# Super-Regenerative-FM-Tuner-ForcedQuench.net
KiCad netlist of a schematic drawn in EAGLE
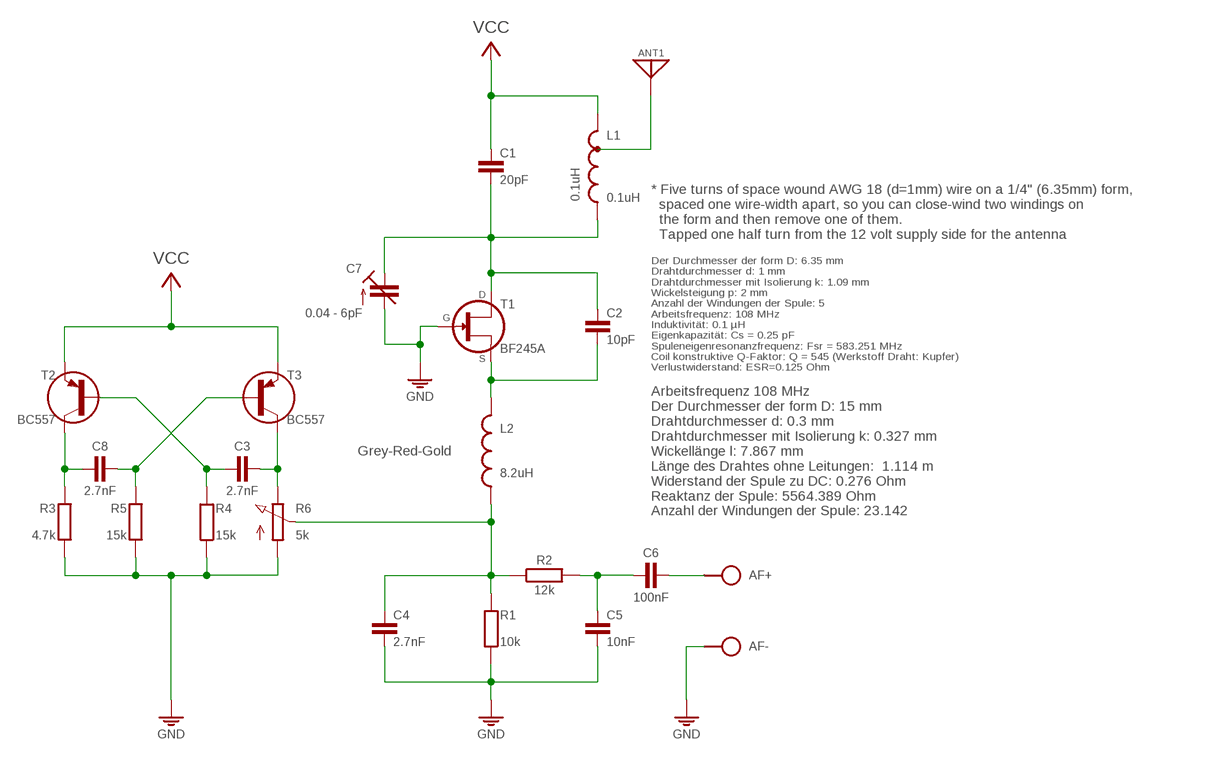
[diagram p0: schematic, sheet 1]

(export (version "E")
  (design (tool "Eeschema 10.0.6"))
  (components
    (comp (ref "AF")
      (value "SPAD+-+-")
      (footprint "eagle-import:SPAD+-")
      (libsource (lib "eagle-import") (part "SPAD+-+-"))
    )
    (comp (ref "ANT1")
      (value "ANT")
      (footprint "eagle-import:SPAD")
      (libsource (lib "eagle-import") (part "ANT"))
    )
    (comp (ref "C1")
      (value "20pF")
      (footprint "eagle-import:C025-015X024")
      (libsource (lib "eagle-import") (part "C025-015X024"))
    )
    (comp (ref "C2")
      (value "10pF")
      (footprint "eagle-import:C025-015X024")
      (libsource (lib "eagle-import") (part "C025-015X024"))
    )
    (comp (ref "C3")
      (value "2.7nF")
      (footprint "eagle-import:C0750-020X044")
      (libsource (lib "eagle-import") (part "C-H075-020X044"))
    )
    (comp (ref "C4")
      (value "2.7nF")
      (footprint "eagle-import:C050-020X044@1")
      (libsource (lib "eagle-import") (part "C050-020X044"))
    )
    (comp (ref "C5")
      (value "10nF")
      (footprint "eagle-import:C050-020X044@1")
      (libsource (lib "eagle-import") (part "C050-020X044"))
    )
    (comp (ref "C6")
      (value "100nF")
      (footprint "eagle-import:C050-020X044")
      (libsource (lib "eagle-import") (part "C-H050-020X044"))
    )
    (comp (ref "C7")
      (value "0.04 - 6pF")
      (footprint "eagle-import:CTRIMTZ03")
      (libsource (lib "eagle-import") (part "C-TR-PH20127-TZ03"))
    )
    (comp (ref "C8")
      (value "2.7nF")
      (footprint "eagle-import:C0750-020X044")
      (libsource (lib "eagle-import") (part "C-H075-020X044"))
    )
    (comp (ref "L1")
      (value "0.1uH")
      (footprint "eagle-import:L-08_12-TAP1")
      (libsource (lib "eagle-import") (part "L-TAP1L-08/12-TAP1"))
    )
    (comp (ref "L2")
      (value "8.2uH")
      (footprint "eagle-import:L-04_7-V")
      (libsource (lib "eagle-import") (part "L04/7-V"))
    )
    (comp (ref "PWR")
      (value "VCC_GNDL")
      (footprint "eagle-import:SPAD-+")
      (libsource (lib "eagle-import") (part "VCC_GNDL"))
    )
    (comp (ref "R1")
      (value "10k")
      (footprint "eagle-import:0204_7")
      (libsource (lib "eagle-import") (part "R0204/7"))
    )
    (comp (ref "R2")
      (value "12k")
      (footprint "eagle-import:0204_7")
      (libsource (lib "eagle-import") (part "R-H0204/7"))
    )
    (comp (ref "R3")
      (value "4.7k")
      (footprint "eagle-import:0202_7-V")
      (libsource (lib "eagle-import") (part "R0202/7-V"))
    )
    (comp (ref "R4")
      (value "15k")
      (footprint "eagle-import:0202_7-V")
      (libsource (lib "eagle-import") (part "R0202/7-V"))
    )
    (comp (ref "R5")
      (value "15k")
      (footprint "eagle-import:0202_7-V")
      (libsource (lib "eagle-import") (part "R0202/7-V"))
    )
    (comp (ref "R6")
      (value "5k")
      (footprint "eagle-import:POT-V")
      (libsource (lib "eagle-import") (part "POT-V"))
    )
    (comp (ref "T1")
      (value "BF245A")
      (footprint "eagle-import:TO92-GSD")
      (libsource (lib "eagle-import") (part "BF245BTO92"))
    )
    (comp (ref "T2")
      (value "BC557")
      (footprint "eagle-import:TO92-CBE")
      (libsource (lib "eagle-import") (part "BC557CBE"))
    )
    (comp (ref "T3")
      (value "BC557")
      (footprint "eagle-import:TO92-CBE")
      (libsource (lib "eagle-import") (part "BC557CBE"))
    )
  )
  (nets
    (net (code "1") (name "GND") (class "Default")
      (node (ref "AF") (pin "1") (pinfunction "P$1_1") (pintype "passive"))
      (node (ref "C4") (pin "2") (pinfunction "2_2") (pintype "passive"))
      (node (ref "C5") (pin "2") (pinfunction "2_2") (pintype "passive"))
      (node (ref "C7") (pin "1") (pinfunction "A_1") (pintype "passive"))
      (node (ref "PWR") (pin "1") (pinfunction "GND_1") (pintype "power_in"))
      (node (ref "R1") (pin "1") (pinfunction "2_1") (pintype "passive"))
      (node (ref "R3") (pin "1") (pinfunction "2_1") (pintype "passive"))
      (node (ref "R4") (pin "1") (pinfunction "2_1") (pintype "passive"))
      (node (ref "R5") (pin "1") (pinfunction "2_1") (pintype "passive"))
      (node (ref "R6") (pin "A") (pinfunction "A_A") (pintype "passive"))
      (node (ref "T1") (pin "1") (pinfunction "G_1") (pintype "passive"))
    )
    (net (code "2") (name "Net-(AFA-P$1)") (class "Default")
      (node (ref "AF") (pin "2") (pinfunction "P$1_2") (pintype "passive"))
      (node (ref "C6") (pin "2") (pinfunction "2_2") (pintype "passive"))
    )
    (net (code "3") (name "Net-(C3-Pad2)") (class "Default")
      (node (ref "C3") (pin "2") (pinfunction "2_2") (pintype "passive"))
      (node (ref "R6") (pin "E") (pinfunction "E_E") (pintype "passive"))
      (node (ref "T3") (pin "C") (pinfunction "C_C") (pintype "passive"))
    )
    (net (code "4") (name "Net-(C5-Pad1)") (class "Default")
      (node (ref "C5") (pin "1") (pinfunction "1_1") (pintype "passive"))
      (node (ref "C6") (pin "1") (pinfunction "1_1") (pintype "passive"))
      (node (ref "R2") (pin "2") (pinfunction "2_2") (pintype "passive"))
    )
    (net (code "5") (name "Net-(C7-E)") (class "Default")
      (node (ref "C1") (pin "2") (pinfunction "2_2") (pintype "passive"))
      (node (ref "C2") (pin "1") (pinfunction "1_1") (pintype "passive"))
      (node (ref "C7") (pin "2") (pinfunction "E_2") (pintype "passive"))
      (node (ref "L1") (pin "2") (pinfunction "2_2") (pintype "passive"))
      (node (ref "T1") (pin "3") (pinfunction "D_3") (pintype "passive"))
    )
    (net (code "6") (name "Net-(L1-T)") (class "Default")
      (node (ref "ANT1") (pin "1") (pinfunction "1_1") (pintype "output"))
      (node (ref "L1") (pin "3") (pinfunction "T_3") (pintype "passive"))
    )
    (net (code "7") (name "Net-(R1-1)") (class "Default")
      (node (ref "C4") (pin "1") (pinfunction "1_1") (pintype "passive"))
      (node (ref "L2") (pin "2") (pinfunction "2_2") (pintype "passive"))
      (node (ref "R1") (pin "2") (pinfunction "1_2") (pintype "passive"))
      (node (ref "R2") (pin "1") (pinfunction "1_1") (pintype "passive"))
      (node (ref "R6") (pin "S") (pinfunction "S_S") (pintype "passive"))
    )
    (net (code "8") (name "Net-(R3-1)") (class "Default")
      (node (ref "C8") (pin "1") (pinfunction "1_1") (pintype "passive"))
      (node (ref "R3") (pin "2") (pinfunction "1_2") (pintype "passive"))
      (node (ref "T2") (pin "C") (pinfunction "C_C") (pintype "passive"))
    )
    (net (code "9") (name "Net-(R4-1)") (class "Default")
      (node (ref "C3") (pin "1") (pinfunction "1_1") (pintype "passive"))
      (node (ref "R4") (pin "2") (pinfunction "1_2") (pintype "passive"))
      (node (ref "T2") (pin "B") (pinfunction "B_B") (pintype "passive"))
    )
    (net (code "10") (name "Net-(R5-1)") (class "Default")
      (node (ref "C8") (pin "2") (pinfunction "2_2") (pintype "passive"))
      (node (ref "R5") (pin "2") (pinfunction "1_2") (pintype "passive"))
      (node (ref "T3") (pin "B") (pinfunction "B_B") (pintype "passive"))
    )
    (net (code "11") (name "Net-(T1-S)") (class "Default")
      (node (ref "C2") (pin "2") (pinfunction "2_2") (pintype "passive"))
      (node (ref "L2") (pin "1") (pinfunction "1_1") (pintype "passive"))
      (node (ref "T1") (pin "2") (pinfunction "S_2") (pintype "passive"))
    )
    (net (code "12") (name "VCC") (class "Default")
      (node (ref "C1") (pin "1") (pinfunction "1_1") (pintype "passive"))
      (node (ref "L1") (pin "1") (pinfunction "1_1") (pintype "passive"))
      (node (ref "PWR") (pin "2") (pinfunction "VCC_2") (pintype "power_in"))
      (node (ref "T2") (pin "E") (pinfunction "E_E") (pintype "passive"))
      (node (ref "T3") (pin "E") (pinfunction "E_E") (pintype "passive"))
    )
  )
)
